# USB.net
KiCad netlist of a schematic drawn in Altium Designer
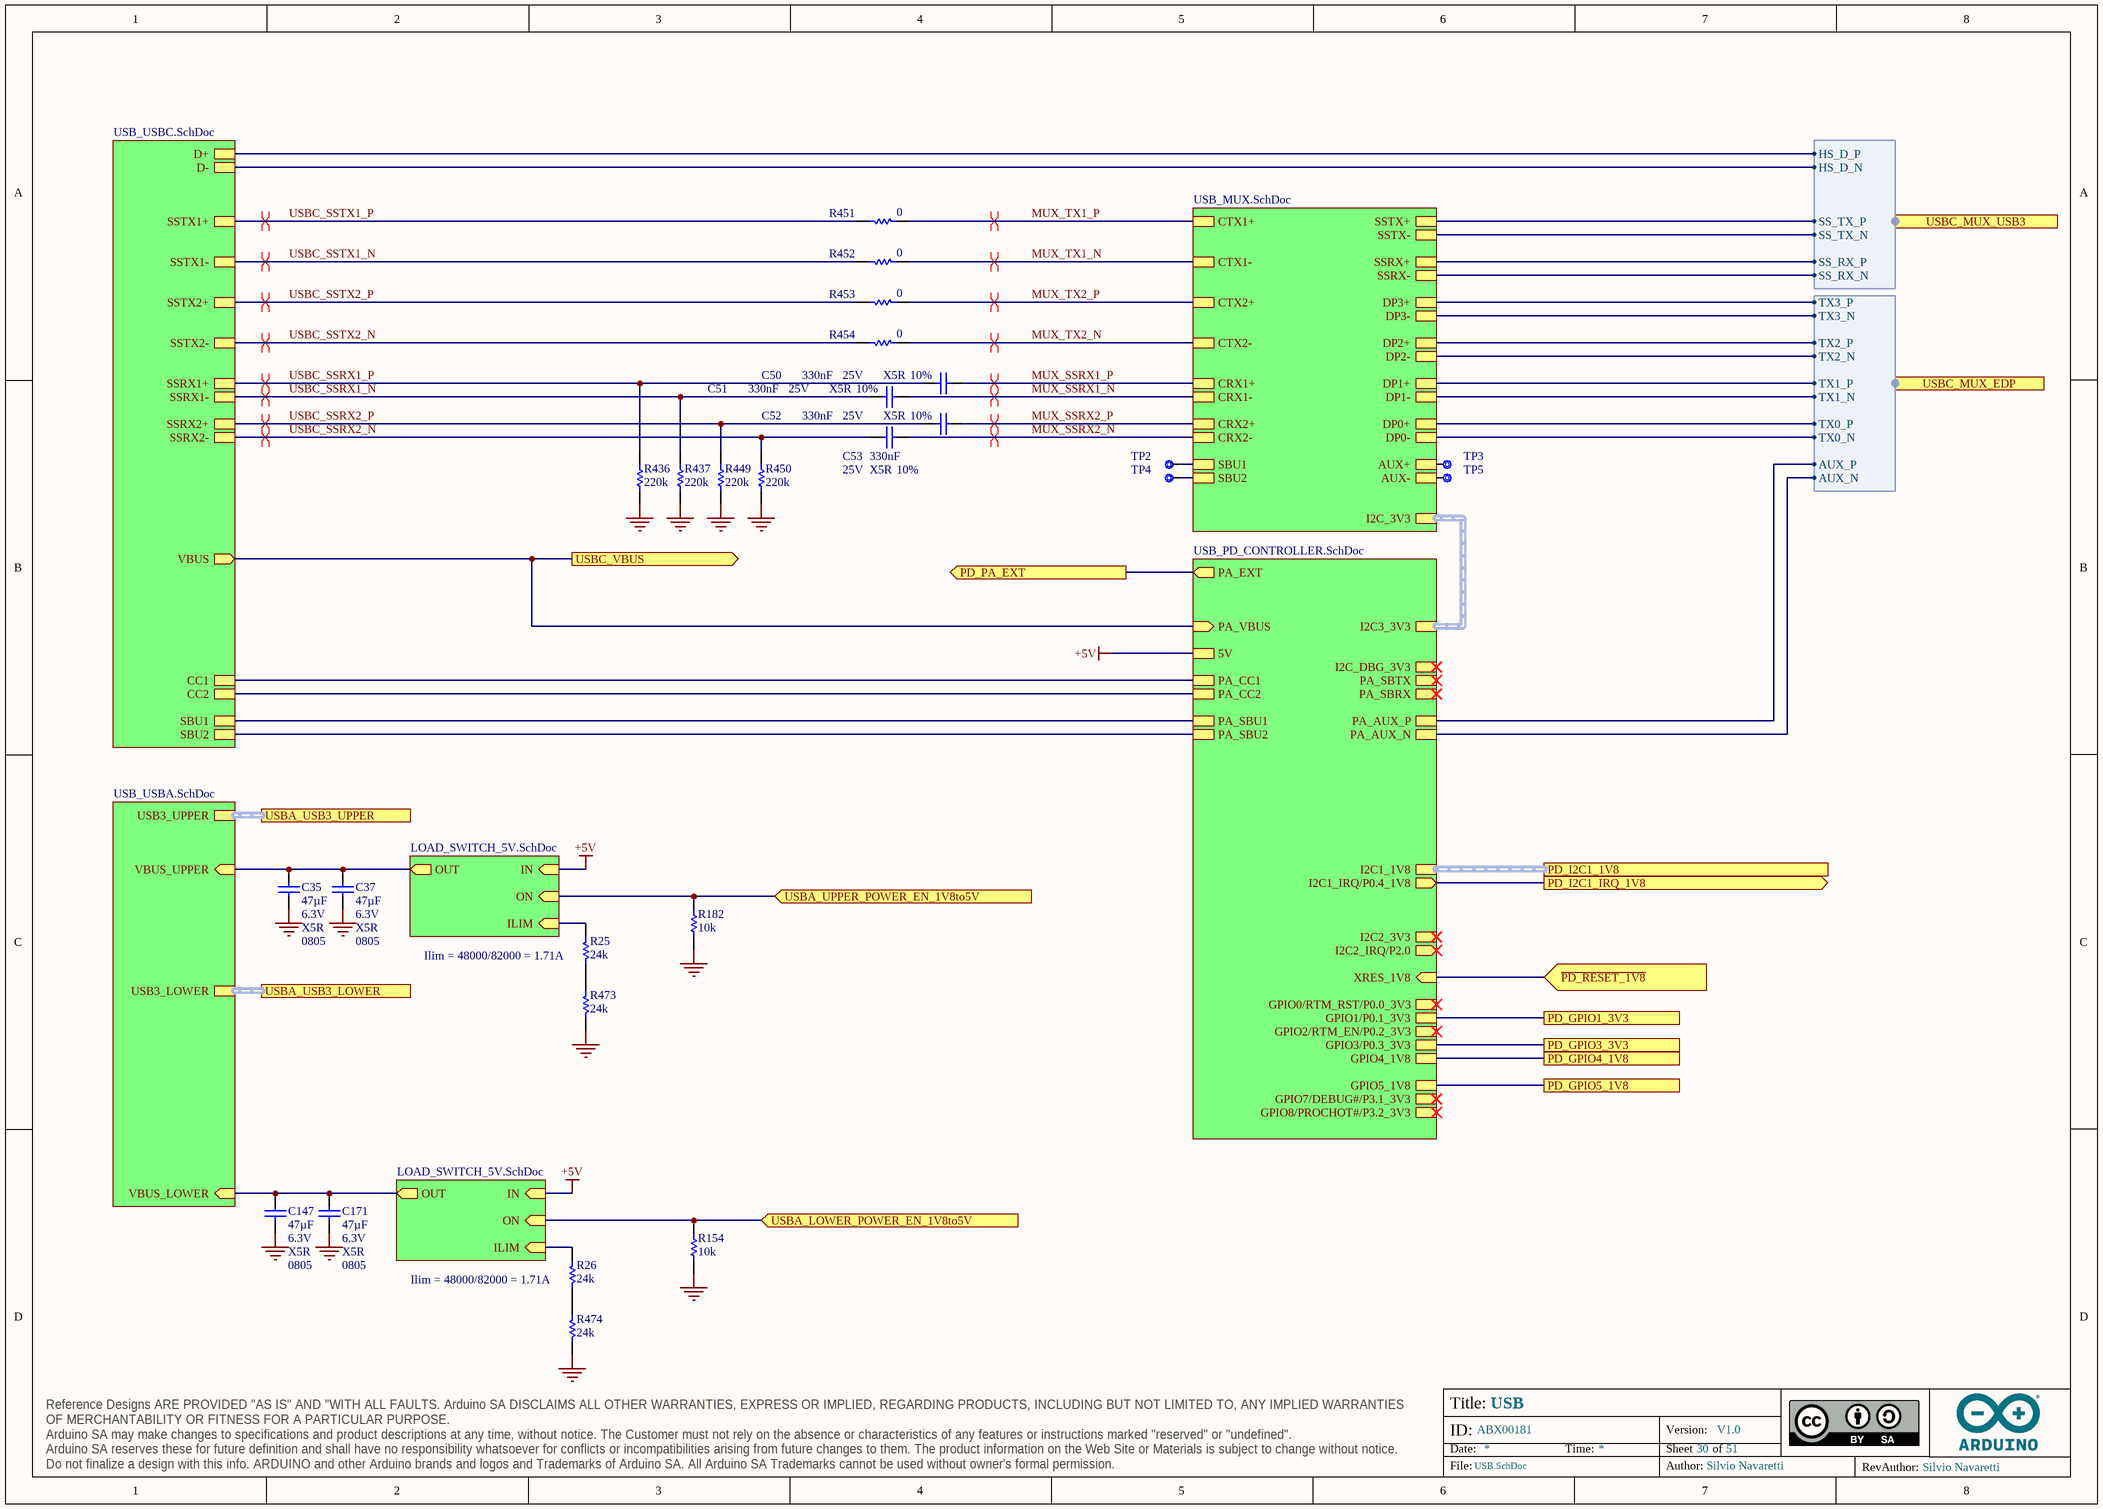
[diagram p0: USB.SchDoc]

(export (version "E")
  (design (tool "Eeschema 10.0.6"))
  (components
    (comp (ref "C35")
      (value "47µF")
      (footprint "CAP-0805")
      (description "CAP CHIP 0805 47uF 20% 6.3V X5R")
      (fields
        (field (name "VOLTAGE") "6.3V")
        (field (name "DIELECTRIC") "X5R")
        (field (name "TOLERANCE") "20%")
        (field (name "CASE CODE (IMPERIAL)") "0805")
        (field (name "MANUFACTURER") "KEMET")
      )
      (libsource (lib "Clean") (part "CAP"))
    )
    (comp (ref "C37")
      (value "47µF")
      (footprint "CAP-0805")
      (description "CAP CHIP 0805 47uF 20% 6.3V X5R")
      (fields
        (field (name "VOLTAGE") "6.3V")
        (field (name "DIELECTRIC") "X5R")
        (field (name "TOLERANCE") "20%")
        (field (name "CASE CODE (IMPERIAL)") "0805")
        (field (name "MANUFACTURER") "KEMET")
      )
      (libsource (lib "Clean") (part "CAP"))
    )
    (comp (ref "C50")
      (value "330nF")
      (footprint "CAP-0201")
      (description "CAP CHIP 0201 330nF 10% 25V X5R")
      (fields
        (field (name "VOLTAGE") "25V")
        (field (name "DIELECTRIC") "X5R")
        (field (name "TOLERANCE") "10%")
        (field (name "MANUFACTURER") "Samsung Electro-Mechanics")
        (field (name "PART NUMBER") "CL03A334KA3NRNC")
      )
      (libsource (lib "Clean") (part "CAP"))
    )
    (comp (ref "C51")
      (value "330nF")
      (footprint "CAP-0201")
      (description "CAP CHIP 0201 330nF 10% 25V X5R")
      (fields
        (field (name "VOLTAGE") "25V")
        (field (name "DIELECTRIC") "X5R")
        (field (name "TOLERANCE") "10%")
        (field (name "MANUFACTURER") "Samsung Electro-Mechanics")
        (field (name "PART NUMBER") "CL03A334KA3NRNC")
      )
      (libsource (lib "Clean") (part "CAP"))
    )
    (comp (ref "C52")
      (value "330nF")
      (footprint "CAP-0201")
      (description "CAP CHIP 0201 330nF 10% 25V X5R")
      (fields
        (field (name "VOLTAGE") "25V")
        (field (name "DIELECTRIC") "X5R")
        (field (name "TOLERANCE") "10%")
        (field (name "MANUFACTURER") "Samsung Electro-Mechanics")
        (field (name "PART NUMBER") "CL03A334KA3NRNC")
      )
      (libsource (lib "Clean") (part "CAP"))
    )
    (comp (ref "C53")
      (value "330nF")
      (footprint "CAP-0201")
      (description "CAP CHIP 0201 330nF 10% 25V X5R")
      (fields
        (field (name "VOLTAGE") "25V")
        (field (name "DIELECTRIC") "X5R")
        (field (name "TOLERANCE") "10%")
        (field (name "MANUFACTURER") "Samsung Electro-Mechanics")
        (field (name "PART NUMBER") "CL03A334KA3NRNC")
      )
      (libsource (lib "Clean") (part "CAP"))
    )
    (comp (ref "C147")
      (value "47µF")
      (footprint "CAP-0805")
      (description "CAP CHIP 0805 47uF 20% 6.3V X5R")
      (fields
        (field (name "VOLTAGE") "6.3V")
        (field (name "DIELECTRIC") "X5R")
        (field (name "TOLERANCE") "20%")
        (field (name "CASE CODE (IMPERIAL)") "0805")
        (field (name "MANUFACTURER") "KEMET")
      )
      (libsource (lib "Clean") (part "CAP"))
    )
    (comp (ref "C171")
      (value "47µF")
      (footprint "CAP-0805")
      (description "CAP CHIP 0805 47uF 20% 6.3V X5R")
      (fields
        (field (name "VOLTAGE") "6.3V")
        (field (name "DIELECTRIC") "X5R")
        (field (name "TOLERANCE") "20%")
        (field (name "CASE CODE (IMPERIAL)") "0805")
        (field (name "MANUFACTURER") "KEMET")
      )
      (libsource (lib "Clean") (part "CAP"))
    )
    (comp (ref "R25")
      (value "24k")
      (footprint "RES-0201")
      (description "RES CHIP 0201 24k 1% 1/20W")
      (fields (field (name "POWER") "50mW") (field (name "TOLERANCE") "1%"))
      (libsource (lib "Clean") (part "RES"))
    )
    (comp (ref "R26")
      (value "24k")
      (footprint "RES-0201")
      (description "RES CHIP 0201 24k 1% 1/20W")
      (fields (field (name "POWER") "50mW") (field (name "TOLERANCE") "1%"))
      (libsource (lib "Clean") (part "RES"))
    )
    (comp (ref "R154")
      (value "10k")
      (footprint "RES-0201")
      (description "RES CHIP 0201 10k 1% 1/20W")
      (fields (field (name "POWER") "50mW") (field (name "TOLERANCE") "1%"))
      (libsource (lib "Clean") (part "RES"))
    )
    (comp (ref "R182")
      (value "10k")
      (footprint "RES-0201")
      (description "RES CHIP 0201 10k 1% 1/20W")
      (fields (field (name "POWER") "50mW") (field (name "TOLERANCE") "1%"))
      (libsource (lib "Clean") (part "RES"))
    )
    (comp (ref "R436")
      (value "220k")
      (footprint "RES-0201")
      (description "RES CHIP 0201 220k 1% 1/20W")
      (fields (field (name "PART NUMBER") "AC0201FR-07220KL") (field (name "TOLERANCE") "1%"))
      (libsource (lib "Clean") (part "RES"))
    )
    (comp (ref "R437")
      (value "220k")
      (footprint "RES-0201")
      (description "RES CHIP 0201 220k 1% 1/20W")
      (fields (field (name "PART NUMBER") "AC0201FR-07220KL") (field (name "TOLERANCE") "1%"))
      (libsource (lib "Clean") (part "RES"))
    )
    (comp (ref "R449")
      (value "220k")
      (footprint "RES-0201")
      (description "RES CHIP 0201 220k 1% 1/20W")
      (fields (field (name "PART NUMBER") "AC0201FR-07220KL") (field (name "TOLERANCE") "1%"))
      (libsource (lib "Clean") (part "RES"))
    )
    (comp (ref "R450")
      (value "220k")
      (footprint "RES-0201")
      (description "RES CHIP 0201 220k 1% 1/20W")
      (fields (field (name "PART NUMBER") "AC0201FR-07220KL") (field (name "TOLERANCE") "1%"))
      (libsource (lib "Clean") (part "RES"))
    )
    (comp (ref "R451")
      (value "0")
      (footprint "RES-0201")
      (description "RES CHIP 0201 0R")
      (fields (field (name "MANUFACTURER") "Vishay") (field (name "TOLERANCE") "0%"))
      (libsource (lib "Clean") (part "RES"))
    )
    (comp (ref "R452")
      (value "0")
      (footprint "RES-0201")
      (description "RES CHIP 0201 0R")
      (fields (field (name "MANUFACTURER") "Vishay") (field (name "TOLERANCE") "0%"))
      (libsource (lib "Clean") (part "RES"))
    )
    (comp (ref "R453")
      (value "0")
      (footprint "RES-0201")
      (description "RES CHIP 0201 0R")
      (fields (field (name "MANUFACTURER") "Vishay") (field (name "TOLERANCE") "0%"))
      (libsource (lib "Clean") (part "RES"))
    )
    (comp (ref "R454")
      (value "0")
      (footprint "RES-0201")
      (description "RES CHIP 0201 0R")
      (fields (field (name "MANUFACTURER") "Vishay") (field (name "TOLERANCE") "0%"))
      (libsource (lib "Clean") (part "RES"))
    )
    (comp (ref "R473")
      (value "24k")
      (footprint "RES-0201")
      (description "RES CHIP 0201 24k 1% 1/20W")
      (fields (field (name "POWER") "50mW") (field (name "TOLERANCE") "1%"))
      (libsource (lib "Clean") (part "RES"))
    )
    (comp (ref "R474")
      (value "24k")
      (footprint "RES-0201")
      (description "RES CHIP 0201 24k 1% 1/20W")
      (fields (field (name "POWER") "50mW") (field (name "TOLERANCE") "1%"))
      (libsource (lib "Clean") (part "RES"))
    )
    (comp (ref "TP2")
      (value "Test point 1.00mm")
      (footprint "TP-1.00MM")
      (fields (field (name "PART NUMBER") "This is not a component"))
      (libsource (lib "Clean") (part "TESTPOINT"))
    )
    (comp (ref "TP3")
      (value "Test point 1.00mm")
      (footprint "TP-1.00MM")
      (fields (field (name "PART NUMBER") "This is not a component"))
      (libsource (lib "Clean") (part "TESTPOINT"))
    )
    (comp (ref "TP4")
      (value "Test point 1.00mm")
      (footprint "TP-1.00MM")
      (fields (field (name "PART NUMBER") "This is not a component"))
      (libsource (lib "Clean") (part "TESTPOINT"))
    )
    (comp (ref "TP5")
      (value "Test point 1.00mm")
      (footprint "TP-1.00MM")
      (fields (field (name "PART NUMBER") "This is not a component"))
      (libsource (lib "Clean") (part "TESTPOINT"))
    )
  )
  (nets
    (net (code "7") (name "/AUX+") (class "Default")
      (node (ref "TP3") (pin "X") (pinfunction "X_X") (pintype "passive"))
    )
    (net (code "8") (name "/AUX-") (class "Default")
      (node (ref "TP5") (pin "X") (pinfunction "X_X") (pintype "passive"))
    )
    (net (code "29") (name "/ILIM") (class "Default")
      (node (ref "R26") (pin "2") (pinfunction "2_2") (pintype "passive"))
    )
    (net (code "30") (name "/ILIM_1") (class "Default")
      (node (ref "R25") (pin "2") (pinfunction "2_2") (pintype "passive"))
    )
    (net (code "31") (name "/MUX_SSRX1_N") (class "Default")
      (node (ref "C51") (pin "1") (pinfunction "1_1") (pintype "passive"))
    )
    (net (code "32") (name "/MUX_SSRX1_P") (class "Default")
      (node (ref "C50") (pin "1") (pinfunction "1_1") (pintype "passive"))
    )
    (net (code "33") (name "/MUX_SSRX2_N") (class "Default")
      (node (ref "C53") (pin "1") (pinfunction "1_1") (pintype "passive"))
    )
    (net (code "34") (name "/MUX_SSRX2_P") (class "Default")
      (node (ref "C52") (pin "1") (pinfunction "1_1") (pintype "passive"))
    )
    (net (code "35") (name "/MUX_TX1_N") (class "Default")
      (node (ref "R452") (pin "2") (pinfunction "2_2") (pintype "passive"))
    )
    (net (code "36") (name "/MUX_TX1_P") (class "Default")
      (node (ref "R451") (pin "2") (pinfunction "2_2") (pintype "passive"))
    )
    (net (code "37") (name "/MUX_TX2_N") (class "Default")
      (node (ref "R454") (pin "2") (pinfunction "2_2") (pintype "passive"))
    )
    (net (code "38") (name "/MUX_TX2_P") (class "Default")
      (node (ref "R453") (pin "2") (pinfunction "2_2") (pintype "passive"))
    )
    (net (code "39") (name "/OUT") (class "Default")
      (node (ref "C147") (pin "2") (pinfunction "2_2") (pintype "passive"))
      (node (ref "C171") (pin "2") (pinfunction "2_2") (pintype "passive"))
    )
    (net (code "40") (name "/OUT_1") (class "Default")
      (node (ref "C35") (pin "2") (pinfunction "2_2") (pintype "passive"))
      (node (ref "C37") (pin "2") (pinfunction "2_2") (pintype "passive"))
    )
    (net (code "54") (name "/SBU1") (class "Default")
      (node (ref "TP2") (pin "X") (pinfunction "X_X") (pintype "passive"))
    )
    (net (code "55") (name "/SBU2") (class "Default")
      (node (ref "TP4") (pin "X") (pinfunction "X_X") (pintype "passive"))
    )
    (net (code "60") (name "/USBA_LOWER_POWER_EN_1V8to5V") (class "Default")
      (node (ref "R154") (pin "2") (pinfunction "2_2") (pintype "passive"))
    )
    (net (code "61") (name "/USBA_UPPER_POWER_EN_1V8to5V") (class "Default")
      (node (ref "R182") (pin "2") (pinfunction "2_2") (pintype "passive"))
    )
    (net (code "65") (name "/USBC_SSRX1_N") (class "Default")
      (node (ref "C51") (pin "2") (pinfunction "2_2") (pintype "passive"))
      (node (ref "R437") (pin "1") (pinfunction "1_1") (pintype "passive"))
    )
    (net (code "66") (name "/USBC_SSRX1_P") (class "Default")
      (node (ref "C50") (pin "2") (pinfunction "2_2") (pintype "passive"))
      (node (ref "R436") (pin "1") (pinfunction "1_1") (pintype "passive"))
    )
    (net (code "67") (name "/USBC_SSRX2_N") (class "Default")
      (node (ref "C53") (pin "2") (pinfunction "2_2") (pintype "passive"))
      (node (ref "R450") (pin "1") (pinfunction "1_1") (pintype "passive"))
    )
    (net (code "68") (name "/USBC_SSRX2_P") (class "Default")
      (node (ref "C52") (pin "2") (pinfunction "2_2") (pintype "passive"))
      (node (ref "R449") (pin "1") (pinfunction "1_1") (pintype "passive"))
    )
    (net (code "69") (name "/USBC_SSTX1_N") (class "Default")
      (node (ref "R452") (pin "1") (pinfunction "1_1") (pintype "passive"))
    )
    (net (code "70") (name "/USBC_SSTX1_P") (class "Default")
      (node (ref "R451") (pin "1") (pinfunction "1_1") (pintype "passive"))
    )
    (net (code "71") (name "/USBC_SSTX2_N") (class "Default")
      (node (ref "R454") (pin "1") (pinfunction "1_1") (pintype "passive"))
    )
    (net (code "72") (name "/USBC_SSTX2_P") (class "Default")
      (node (ref "R453") (pin "1") (pinfunction "1_1") (pintype "passive"))
    )
    (net (code "76") (name "GND") (class "Default")
      (node (ref "C147") (pin "1") (pinfunction "1_1") (pintype "passive"))
      (node (ref "C171") (pin "1") (pinfunction "1_1") (pintype "passive"))
      (node (ref "C35") (pin "1") (pinfunction "1_1") (pintype "passive"))
      (node (ref "C37") (pin "1") (pinfunction "1_1") (pintype "passive"))
      (node (ref "R154") (pin "1") (pinfunction "1_1") (pintype "passive"))
      (node (ref "R182") (pin "1") (pinfunction "1_1") (pintype "passive"))
      (node (ref "R436") (pin "2") (pinfunction "2_2") (pintype "passive"))
      (node (ref "R437") (pin "2") (pinfunction "2_2") (pintype "passive"))
      (node (ref "R449") (pin "2") (pinfunction "2_2") (pintype "passive"))
      (node (ref "R450") (pin "2") (pinfunction "2_2") (pintype "passive"))
      (node (ref "R473") (pin "1") (pinfunction "1_1") (pintype "passive"))
      (node (ref "R474") (pin "1") (pinfunction "1_1") (pintype "passive"))
    )
    (net (code "77") (name "Net-(R25-Pad1)") (class "Default")
      (node (ref "R25") (pin "1") (pinfunction "1_1") (pintype "passive"))
      (node (ref "R473") (pin "2") (pinfunction "2_2") (pintype "passive"))
    )
    (net (code "78") (name "Net-(R26-Pad1)") (class "Default")
      (node (ref "R26") (pin "1") (pinfunction "1_1") (pintype "passive"))
      (node (ref "R474") (pin "2") (pinfunction "2_2") (pintype "passive"))
    )
  )
)
